# PR5001_Mini_Breakout_Shield.net
KiCad netlist of a schematic drawn in EAGLE
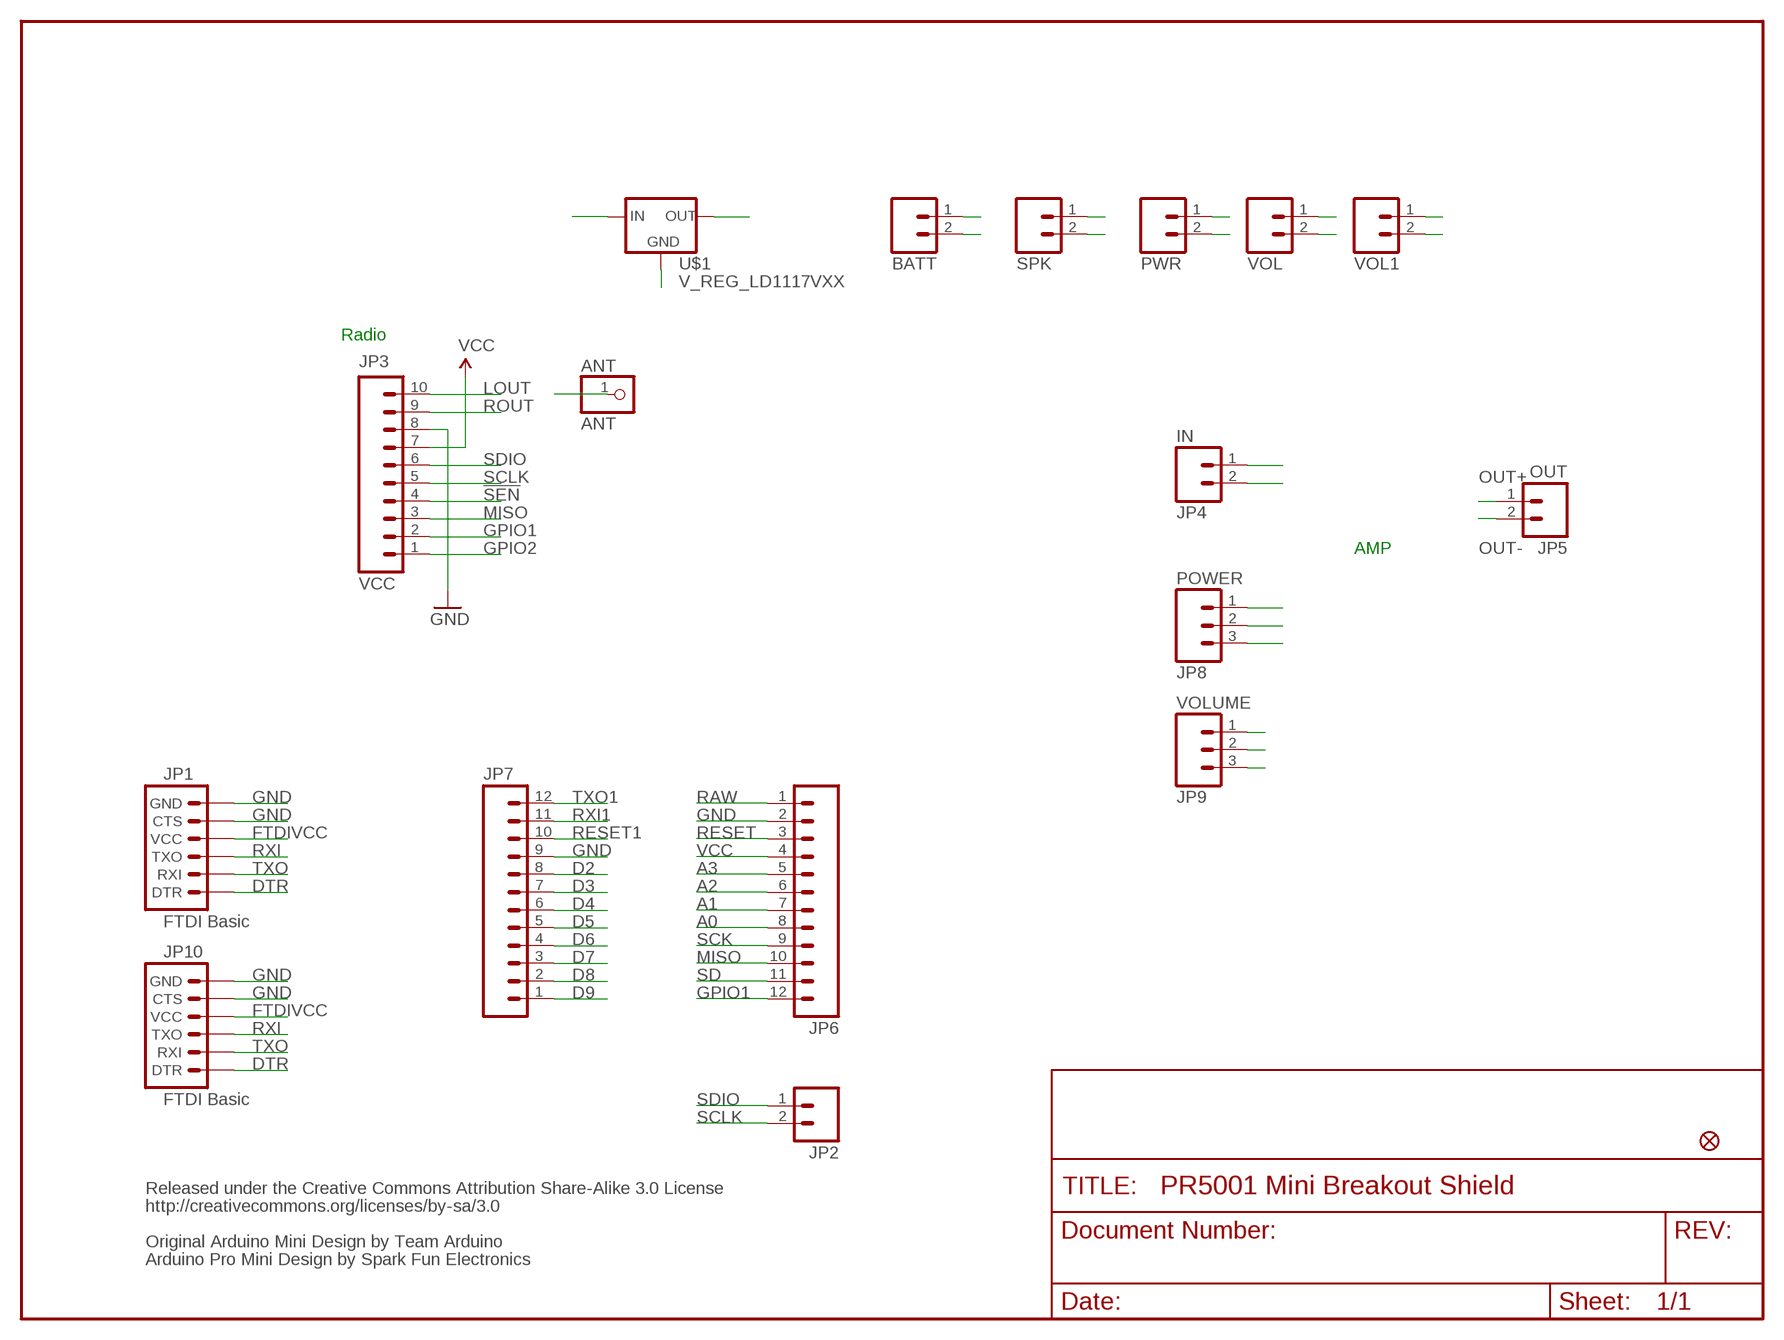
[diagram p0: schematic, sheet 1]

(export (version "E")
  (design (tool "Eeschema 10.0.6"))
  (components
    (comp (ref "ANT")
      (value "ANT")
      (footprint "eagle-import:1X01")
      (libsource (lib "eagle-import") (part "PINHD-1X1"))
    )
    (comp (ref "BATT")
      (value "M02PTH")
      (footprint "eagle-import:1X02")
      (libsource (lib "eagle-import") (part "M02PTH"))
    )
    (comp (ref "JP1")
      (value "FTDI Basic")
      (footprint "eagle-import:1X06")
      (libsource (lib "eagle-import") (part "ARDUINO_SERIAL_PROGRAMPTH"))
    )
    (comp (ref "JP2")
      (value "M02PTH")
      (footprint "eagle-import:1X02")
      (libsource (lib "eagle-import") (part "M02PTH"))
    )
    (comp (ref "JP3")
      (value "VCC")
      (footprint "eagle-import:1X10")
      (libsource (lib "eagle-import") (part "M10{dblquote}"))
    )
    (comp (ref "JP4")
      (value "IN")
      (footprint "eagle-import:1X02")
      (libsource (lib "eagle-import") (part "M02PTH"))
    )
    (comp (ref "JP5")
      (value "OUT")
      (footprint "eagle-import:1X02")
      (libsource (lib "eagle-import") (part "M02PTH"))
    )
    (comp (ref "JP6")
      (value "M12PTH")
      (footprint "eagle-import:1X12")
      (libsource (lib "eagle-import") (part "M12PTH"))
    )
    (comp (ref "JP7")
      (value "M12PTH")
      (footprint "eagle-import:1X12")
      (libsource (lib "eagle-import") (part "M12PTH"))
    )
    (comp (ref "JP8")
      (value "POWER")
      (footprint "eagle-import:1X03")
      (libsource (lib "eagle-import") (part "M03PTH"))
    )
    (comp (ref "JP9")
      (value "VOLUME")
      (footprint "eagle-import:1X03")
      (libsource (lib "eagle-import") (part "M03PTH"))
    )
    (comp (ref "JP10")
      (value "FTDI Basic")
      (footprint "eagle-import:1X06")
      (libsource (lib "eagle-import") (part "ARDUINO_SERIAL_PROGRAMPTH"))
    )
    (comp (ref "PWR")
      (value "M02PTH")
      (footprint "eagle-import:1X02")
      (libsource (lib "eagle-import") (part "M02PTH"))
    )
    (comp (ref "SPK")
      (value "M02PTH")
      (footprint "eagle-import:1X02")
      (libsource (lib "eagle-import") (part "M02PTH"))
    )
    (comp (ref "U$1")
      (value "V_REG_LD1117VXX")
      (footprint "eagle-import:78XXL")
      (libsource (lib "eagle-import") (part "V_REG_LD1117VXX"))
    )
    (comp (ref "U$4")
      (value "FIDUCIAL1X2")
      (footprint "eagle-import:FIDUCIAL-1X2")
      (libsource (lib "eagle-import") (part "FIDUCIAL1X2"))
    )
    (comp (ref "VOL")
      (value "M02PTH")
      (footprint "eagle-import:1X02")
      (libsource (lib "eagle-import") (part "M02PTH"))
    )
    (comp (ref "VOL1")
      (value "M02PTH")
      (footprint "eagle-import:1X02")
      (libsource (lib "eagle-import") (part "M02PTH"))
    )
  )
  (nets
    (net (code "1") (name "/A0") (class "Default")
      (node (ref "JP6") (pin "8") (pinfunction "8_8") (pintype "passive"))
    )
    (net (code "2") (name "/A1") (class "Default")
      (node (ref "JP6") (pin "7") (pinfunction "7_7") (pintype "passive"))
    )
    (net (code "3") (name "/A2") (class "Default")
      (node (ref "JP6") (pin "6") (pinfunction "6_6") (pintype "passive"))
    )
    (net (code "4") (name "/A3") (class "Default")
      (node (ref "JP6") (pin "5") (pinfunction "5_5") (pintype "passive"))
    )
    (net (code "5") (name "/ANT") (class "Default")
      (node (ref "ANT") (pin "1") (pinfunction "1_1") (pintype "passive"))
      (node (ref "VOL1") (pin "2") (pinfunction "2_2") (pintype "passive"))
    )
    (net (code "6") (name "/BATT+") (class "Default")
      (node (ref "BATT") (pin "1") (pinfunction "1_1") (pintype "passive"))
      (node (ref "PWR") (pin "1") (pinfunction "1_1") (pintype "passive"))
    )
    (net (code "7") (name "/D2") (class "Default")
      (node (ref "JP7") (pin "8") (pinfunction "8_8") (pintype "passive"))
    )
    (net (code "8") (name "/D3") (class "Default")
      (node (ref "JP7") (pin "7") (pinfunction "7_7") (pintype "passive"))
    )
    (net (code "9") (name "/D4") (class "Default")
      (node (ref "JP7") (pin "6") (pinfunction "6_6") (pintype "passive"))
    )
    (net (code "10") (name "/D5") (class "Default")
      (node (ref "JP7") (pin "5") (pinfunction "5_5") (pintype "passive"))
    )
    (net (code "11") (name "/D6") (class "Default")
      (node (ref "JP7") (pin "4") (pinfunction "4_4") (pintype "passive"))
    )
    (net (code "12") (name "/D7") (class "Default")
      (node (ref "JP7") (pin "3") (pinfunction "3_3") (pintype "passive"))
    )
    (net (code "13") (name "/D8") (class "Default")
      (node (ref "JP7") (pin "2") (pinfunction "2_2") (pintype "passive"))
    )
    (net (code "14") (name "/D9") (class "Default")
      (node (ref "JP7") (pin "1") (pinfunction "1_1") (pintype "passive"))
    )
    (net (code "15") (name "/DTR") (class "Default")
      (node (ref "JP1") (pin "1") (pinfunction "DTR_1") (pintype "passive"))
      (node (ref "JP10") (pin "1") (pinfunction "DTR_1") (pintype "passive"))
    )
    (net (code "16") (name "/FTDIVCC") (class "Default")
      (node (ref "JP1") (pin "4") (pinfunction "VCC_4") (pintype "passive"))
      (node (ref "JP10") (pin "4") (pinfunction "VCC_4") (pintype "passive"))
    )
    (net (code "17") (name "/GPIO1") (class "Default")
      (node (ref "JP3") (pin "2") (pinfunction "2_2") (pintype "passive"))
      (node (ref "JP6") (pin "12") (pinfunction "12_12") (pintype "passive"))
    )
    (net (code "18") (name "/GPIO2") (class "Default")
      (node (ref "JP3") (pin "1") (pinfunction "1_1") (pintype "passive"))
    )
    (net (code "19") (name "/IN") (class "Default")
      (node (ref "JP9") (pin "3") (pinfunction "3_3") (pintype "passive"))
      (node (ref "VOL1") (pin "1") (pinfunction "1_1") (pintype "passive"))
    )
    (net (code "20") (name "/LOUT") (class "Default")
      (node (ref "JP3") (pin "10") (pinfunction "10_10") (pintype "passive"))
      (node (ref "JP4") (pin "1") (pinfunction "1_1") (pintype "passive"))
    )
    (net (code "21") (name "/MISO") (class "Default")
      (node (ref "JP3") (pin "3") (pinfunction "3_3") (pintype "passive"))
      (node (ref "JP6") (pin "10") (pinfunction "10_10") (pintype "passive"))
    )
    (net (code "22") (name "/OPUT") (class "Default")
      (node (ref "JP9") (pin "2") (pinfunction "2_2") (pintype "passive"))
      (node (ref "VOL") (pin "2") (pinfunction "2_2") (pintype "passive"))
    )
    (net (code "23") (name "/OUT+") (class "Default")
      (node (ref "JP5") (pin "1") (pinfunction "1_1") (pintype "passive"))
      (node (ref "SPK") (pin "1") (pinfunction "1_1") (pintype "passive"))
    )
    (net (code "24") (name "/OUT-") (class "Default")
      (node (ref "JP5") (pin "2") (pinfunction "2_2") (pintype "passive"))
      (node (ref "SPK") (pin "2") (pinfunction "2_2") (pintype "passive"))
    )
    (net (code "25") (name "/POT+") (class "Default")
      (node (ref "PWR") (pin "2") (pinfunction "2_2") (pintype "passive"))
      (node (ref "U$1") (pin "OUT") (pinfunction "IN_OUT") (pintype "input"))
    )
    (net (code "26") (name "/RAW") (class "Default")
      (node (ref "JP6") (pin "1") (pinfunction "1_1") (pintype "passive"))
    )
    (net (code "27") (name "/RESET") (class "Default")
      (node (ref "JP6") (pin "3") (pinfunction "3_3") (pintype "passive"))
    )
    (net (code "28") (name "/RESET1") (class "Default")
      (node (ref "JP7") (pin "10") (pinfunction "10_10") (pintype "passive"))
    )
    (net (code "29") (name "/ROUT") (class "Default")
      (node (ref "JP3") (pin "9") (pinfunction "9_9") (pintype "passive"))
    )
    (net (code "30") (name "/RXI") (class "Default")
      (node (ref "JP1") (pin "3") (pinfunction "TXO_3") (pintype "passive"))
      (node (ref "JP10") (pin "3") (pinfunction "TXO_3") (pintype "passive"))
    )
    (net (code "31") (name "/RXI1") (class "Default")
      (node (ref "JP7") (pin "11") (pinfunction "11_11") (pintype "passive"))
    )
    (net (code "32") (name "/SCK") (class "Default")
      (node (ref "JP6") (pin "9") (pinfunction "9_9") (pintype "passive"))
    )
    (net (code "33") (name "/SCLK") (class "Default")
      (node (ref "JP2") (pin "2") (pinfunction "2_2") (pintype "passive"))
      (node (ref "JP3") (pin "5") (pinfunction "5_5") (pintype "passive"))
    )
    (net (code "34") (name "/SD") (class "Default")
      (node (ref "JP6") (pin "11") (pinfunction "11_11") (pintype "passive"))
      (node (ref "JP8") (pin "3") (pinfunction "3_3") (pintype "passive"))
    )
    (net (code "35") (name "/SDIO") (class "Default")
      (node (ref "JP2") (pin "1") (pinfunction "1_1") (pintype "passive"))
      (node (ref "JP3") (pin "6") (pinfunction "6_6") (pintype "passive"))
    )
    (net (code "36") (name "/TXO") (class "Default")
      (node (ref "JP1") (pin "2") (pinfunction "RXI_2") (pintype "passive"))
      (node (ref "JP10") (pin "2") (pinfunction "RXI_2") (pintype "passive"))
    )
    (net (code "37") (name "/TXO1") (class "Default")
      (node (ref "JP7") (pin "12") (pinfunction "12_12") (pintype "passive"))
    )
    (net (code "38") (name "/~{SEN}") (class "Default")
      (node (ref "JP3") (pin "4") (pinfunction "4_4") (pintype "passive"))
    )
    (net (code "39") (name "GND") (class "Default")
      (node (ref "BATT") (pin "2") (pinfunction "2_2") (pintype "passive"))
      (node (ref "JP1") (pin "5") (pinfunction "CTS_5") (pintype "passive"))
      (node (ref "JP1") (pin "6") (pinfunction "GND_6") (pintype "passive"))
      (node (ref "JP10") (pin "5") (pinfunction "CTS_5") (pintype "passive"))
      (node (ref "JP10") (pin "6") (pinfunction "GND_6") (pintype "passive"))
      (node (ref "JP3") (pin "8") (pinfunction "8_8") (pintype "passive"))
      (node (ref "JP4") (pin "2") (pinfunction "2_2") (pintype "passive"))
      (node (ref "JP6") (pin "2") (pinfunction "2_2") (pintype "passive"))
      (node (ref "JP7") (pin "9") (pinfunction "9_9") (pintype "passive"))
      (node (ref "JP8") (pin "1") (pinfunction "1_1") (pintype "passive"))
      (node (ref "JP9") (pin "1") (pinfunction "1_1") (pintype "passive"))
      (node (ref "U$1") (pin "IN") (pinfunction "GND_IN") (pintype "input"))
      (node (ref "VOL") (pin "1") (pinfunction "1_1") (pintype "passive"))
    )
    (net (code "40") (name "VCC") (class "Default")
      (node (ref "JP3") (pin "7") (pinfunction "7_7") (pintype "passive"))
      (node (ref "JP6") (pin "4") (pinfunction "4_4") (pintype "passive"))
      (node (ref "JP8") (pin "2") (pinfunction "2_2") (pintype "passive"))
      (node (ref "U$1") (pin "GND") (pinfunction "OUT_GND") (pintype "output"))
    )
  )
)
